# SatController_S1.net
KiCad netlist of a schematic drawn in Altium Designer
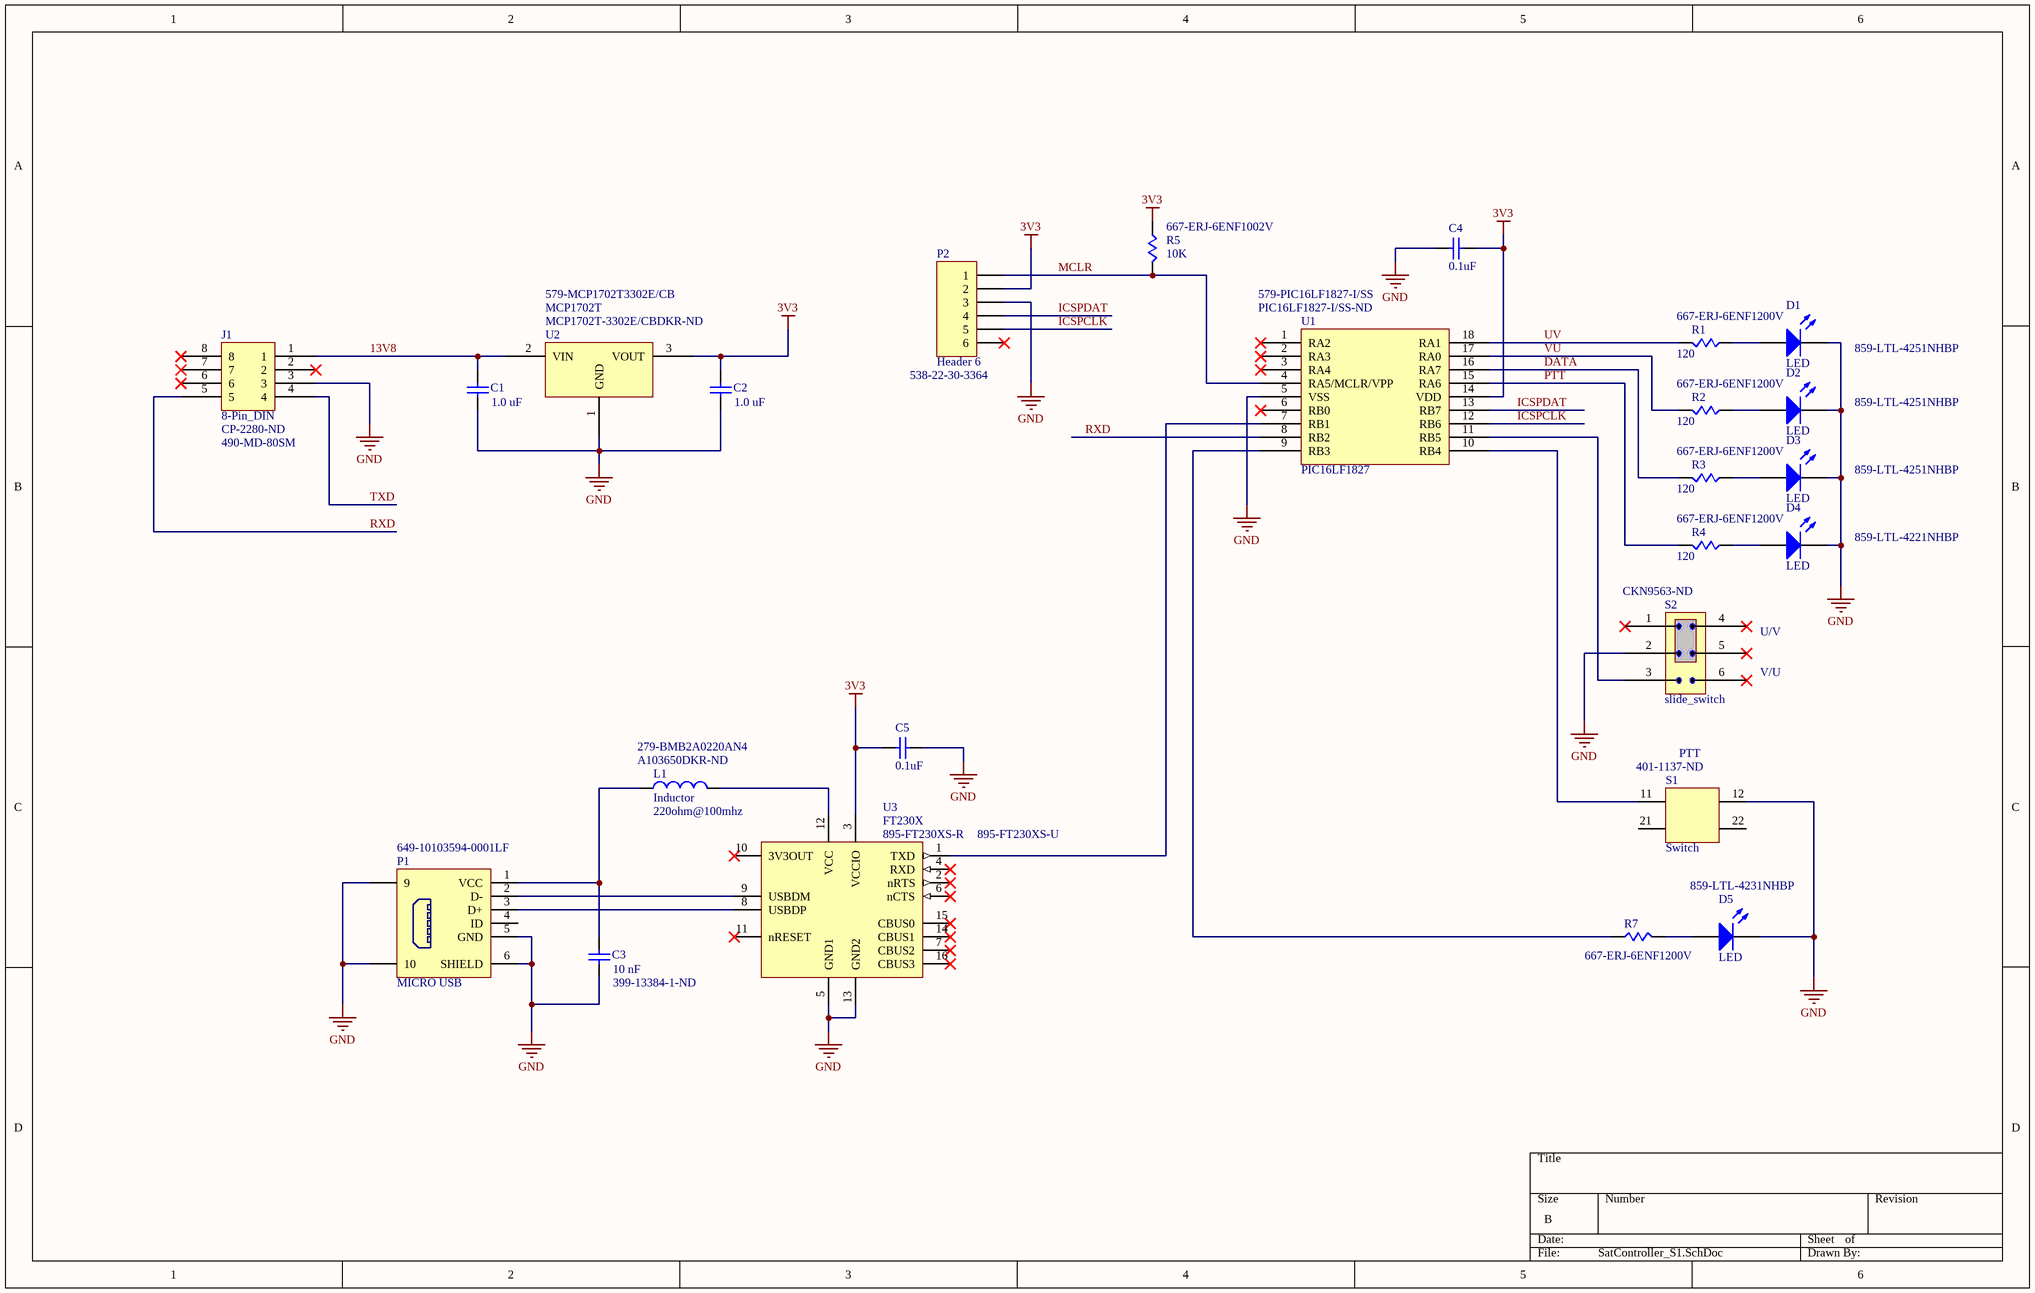
[diagram p0: SatController_S1.SchDoc]

(export (version "E")
  (design (tool "Eeschema 10.0.6"))
  (components
    (comp (ref "C1")
      (value "1.0 uF")
      (footprint "CAPC2012L")
      (libsource (lib "MAST_Library") (part "Cap Semi"))
    )
    (comp (ref "C2")
      (value "~")
      (footprint "CAPC2012L")
      (fields (field (name "VAULE") "1.0 uF"))
      (libsource (lib "MAST_Library") (part "Cap Semi"))
    )
    (comp (ref "C3")
      (value "10 nF")
      (footprint "CAPC1608L")
      (description "CAP CER 1UF 6.3V 10% X5R 0603")
      (fields
        (field (name "SUPPLIER PART NUMBER 1") "399-13384-1-ND")
        (field (name "MANUFACTURER") "Kemet")
        (field (name "MANUFACTURER PART NUMBER") "C0603C103J5JAC7867")
        (field (name "PUBLISHER") "Altium Limited")
      )
      (libsource (lib "MAST_Library") (part "Cap Semi"))
    )
    (comp (ref "C4")
      (value "0.1uF")
      (footprint "CAPC2012L")
      (libsource (lib "MAST_Library") (part "Cap Semi"))
    )
    (comp (ref "C5")
      (value "0.1uF")
      (footprint "CAPC2012L")
      (libsource (lib "MAST_Library") (part "Cap Semi"))
    )
    (comp (ref "D1")
      (value "LED")
      (footprint "LTL-4231HNBP")
      (description "SMD LED")
      (fields
        (field (name "SUPPLIER PART NUMBER 1") "859-LTL-4251NHBP")
        (field (name "MANUFACTURER") "Lite-On")
        (field (name "MANUFACTURER PART NUMBER") "LTL-4251NHBP")
      )
      (libsource (lib "Schlib_HCG") (part "LED3mm-ra"))
    )
    (comp (ref "D2")
      (value "LED")
      (footprint "LTL-4231HNBP")
      (description "SMD LED")
      (fields
        (field (name "SUPPLIER PART NUMBER 1") "859-LTL-4251NHBP")
        (field (name "MANUFACTURER") "Lite-On")
        (field (name "MANUFACTURER PART NUMBER") "LTL-4251NHBP")
      )
      (libsource (lib "Schlib_HCG") (part "LED3mm-ra"))
    )
    (comp (ref "D3")
      (value "LED")
      (footprint "LTL-4231HNBP")
      (description "SMD LED")
      (fields
        (field (name "SUPPLIER PART NUMBER 1") "859-LTL-4251NHBP")
        (field (name "MANUFACTURER") "Lite-On")
        (field (name "MANUFACTURER PART NUMBER") "LTL-4251NHBP")
      )
      (libsource (lib "Schlib_HCG") (part "LED3mm-ra"))
    )
    (comp (ref "D4")
      (value "LED")
      (footprint "LTL-4231HNBP")
      (description "SMD LED")
      (fields
        (field (name "SUPPLIER PART NUMBER 1") "859-LTL-4221NHBP")
        (field (name "MANUFACTURER") "Lite-On")
        (field (name "MANUFACTURER PART NUMBER") "LTL-4221NHBP")
      )
      (libsource (lib "Schlib_HCG") (part "LED3mm-ra"))
    )
    (comp (ref "D5")
      (value "LED")
      (footprint "LTL-4231HNBP")
      (description "SMD LED")
      (fields
        (field (name "SUPPLIER PART NUMBER 1") "859-LTL-4231NHBP")
        (field (name "MANUFACTURER") "Lite-On")
        (field (name "MANUFACTURER PART NUMBER") "LTL-4231NHBP")
      )
      (libsource (lib "Schlib_HCG") (part "LED3mm-ra"))
    )
    (comp (ref "J1")
      (value "8-Pin_DIN")
      (footprint "MD-80SM")
      (fields
        (field (name "SUPPLIER PART NUMBER 1") "CP-2280-ND")
        (field (name "SUPPLIER PART NUMBER 2") "490-MD-80SM")
        (field (name "MANUFACTURER") "CUI")
        (field (name "MANUFACTURER PART NUMBER") "MD-80SM")
      )
      (libsource (lib "Schlib_HCG") (part "8-Pin_DIN"))
    )
    (comp (ref "L1")
      (value "Inductor")
      (footprint "6-0805_N")
      (fields
        (field (name "ALTIUM_VALUE") "220ohm@100mhz")
        (field (name "SUPPLIER PART NUMBER 1") "A103650DKR-ND")
        (field (name "SUPPLIER PART NUMBER 2") "279-BMB2A0220AN4")
        (field (name "MANUFACTURER") "TE Connectivity / Sigma Inductors")
        (field (name "MANUFACTURER PART NUMBER") "BMB2A0220AN4")
        (field (name "TOLERANCE") "25 %")
        (field (name "PUBLISHER") "Altium Limited")
      )
      (libsource (lib "Miscellaneous Devices") (part "Inductor"))
    )
    (comp (ref "P1")
      (value "MICRO USB")
      (footprint "Connector, Micro-USB, 5-pin - prototype")
      (fields
        (field (name "SUPPLIER PART NUMBER 1") "649-10103594-0001LF")
        (field (name "MANUFACTURER") "Amphenol FCI")
        (field (name "MANUFACTURER PART NUMBER") "10103594-0001LF")
        (field (name "Comment") "Micro USB")
      )
      (libsource (lib "Schlib_HCG") (part "Micro USB"))
    )
    (comp (ref "P2")
      (value "Header 6")
      (footprint "HDR1X6")
      (description "Header, 6-Pin")
      (fields
        (field (name "SUPPLIER PART NUMBER 1") "538-22-30-3364")
        (field (name "MANUFACTURER") "Molex")
        (field (name "MANUFACTURER PART NUMBER") "22-30-3364")
        (field (name "PUBLISHER") "Altium Limited")
      )
      (libsource (lib "Schlib_HCG") (part "Header 6"))
    )
    (comp (ref "R1")
      (value "~")
      (footprint "RESC2012L")
      (description "RES 120 OHM 1/10W 1% 0402 SMD")
      (fields
        (field (name "SUPPLIER PART NUMBER 1") "667-ERJ-6ENF1200V")
        (field (name "MANUFACTURER") "Panasonic")
        (field (name "MANUFACTURER PART NUMBER") "ERJ-6ENF1200V")
        (field (name "VAULE") "120")
      )
      (libsource (lib "MAST_Library") (part "R"))
    )
    (comp (ref "R2")
      (value "~")
      (footprint "RESC2012L")
      (description "RES 120 OHM 1/10W 1% 0402 SMD")
      (fields
        (field (name "SUPPLIER PART NUMBER 1") "667-ERJ-6ENF1200V")
        (field (name "MANUFACTURER") "Panasonic")
        (field (name "MANUFACTURER PART NUMBER") "ERJ-6ENF1200V")
        (field (name "VAULE") "120")
      )
      (libsource (lib "MAST_Library") (part "R"))
    )
    (comp (ref "R3")
      (value "~")
      (footprint "RESC2012L")
      (description "RES 120 OHM 1/10W 1% 0402 SMD")
      (fields
        (field (name "SUPPLIER PART NUMBER 1") "667-ERJ-6ENF1200V")
        (field (name "MANUFACTURER") "Panasonic")
        (field (name "MANUFACTURER PART NUMBER") "ERJ-6ENF1200V")
        (field (name "VAULE") "120")
      )
      (libsource (lib "MAST_Library") (part "R"))
    )
    (comp (ref "R4")
      (value "~")
      (footprint "RESC2012L")
      (description "RES 120 OHM 1/10W 1% 0402 SMD")
      (fields
        (field (name "SUPPLIER PART NUMBER 1") "667-ERJ-6ENF1200V")
        (field (name "MANUFACTURER") "Panasonic")
        (field (name "MANUFACTURER PART NUMBER") "ERJ-6ENF1200V")
        (field (name "VAULE") "120")
      )
      (libsource (lib "MAST_Library") (part "R"))
    )
    (comp (ref "R5")
      (value "~")
      (footprint "RESC2012L")
      (description "RES 120 OHM 1/10W 1% 0402 SMD")
      (fields
        (field (name "VAULE") "10K")
        (field (name "SUPPLIER PART NUMBER 1") "667-ERJ-6ENF1002V")
        (field (name "MANUFACTURER") "Panasonic")
        (field (name "MANUFACTURER PART NUMBER") "ERJ-6ENF1002V")
      )
      (libsource (lib "MAST_Library") (part "R"))
    )
    (comp (ref "R7")
      (value "~")
      (footprint "RESC2012L")
      (description "RES 120 OHM 1/10W 1% 0402 SMD")
      (fields
        (field (name "SUPPLIER PART NUMBER 1") "667-ERJ-6ENF1200V")
        (field (name "MANUFACTURER") "Panasonic")
        (field (name "MANUFACTURER PART NUMBER") "ERJ-6ENF1200V")
      )
      (libsource (lib "MAST_Library") (part "R"))
    )
    (comp (ref "S1")
      (value "PVA-KeySwitch")
      (footprint "PVA1_Switch")
      (description "SWITCH PUSH DPST-NO 0.1A 32V")
      (fields
        (field (name "VAULE") "Switch")
        (field (name "SUPPLIER PART NUMBER 1") "401-1137-ND")
        (field (name "MANUFACTURER") "C&K Components")
        (field (name "MANUFACTURER PART NUMBER") "PVA1 OA H3 1.2N V2")
      )
      (libsource (lib "Schlib_HCG") (part "PVA-KeySwitch"))
    )
    (comp (ref "S2")
      (value "slide_switch")
      (footprint "OS202011MA0QN1")
      (description "SWITCH SLIDE DPDT 100MA 12V")
      (fields
        (field (name "SUPPLIER PART NUMBER 1") "CKN9563-ND")
        (field (name "MANUFACTURER") "C&K Components")
        (field (name "MANUFACTURER PART NUMBER") "OS202011MA0QN1")
      )
      (libsource (lib "Schlib_HCG") (part "slide_switch"))
    )
    (comp (ref "U1")
      (value "PIC16LF1827")
      (footprint "SOIC127P1030-18M")
      (fields
        (field (name "SUPPLIER PART NUMBER 2") "PIC16LF1827-I/SS-ND")
        (field (name "MANUFACTURER") "Microchip Technology")
        (field (name "MANUFACTURER PART NUMBER") "PIC16LF1827-I/SS")
        (field (name "SUPPLIER PART NUMBER 3") "579-PIC16LF1827-I/SS")
      )
      (libsource (lib "Schlib_HCG") (part "PIC16LF1827"))
    )
    (comp (ref "U2")
      (value "MCP1702T")
      (footprint "SOT23-3N")
      (fields
        (field (name "SUPPLIER PART NUMBER 1") "MCP1702T-3302E/CBDKR-ND")
        (field (name "SUPPLIER PART NUMBER 2") "579-MCP1702T3302E/CB")
        (field (name "MANUFACTURER") "Microchip Technology")
        (field (name "MANUFACTURER PART NUMBER") "MCP1702T-3302E/CB")
      )
      (libsource (lib "Schlib_HCG") (part "MCP1702T"))
    )
    (comp (ref "U3")
      (value "FT230X")
      (footprint "SOP64P600X175-16N")
      (fields
        (field (name "SUPPLIER PART NUMBER 1") "895-FT230XS-R")
        (field (name "SUPPLIER PART NUMBER 2") "895-FT230XS-U")
        (field (name "MANUFACTURER") "FTDI")
        (field (name "MANUFACTURER PART NUMBER") "FT230XS-U")
      )
      (libsource (lib "Schlib_HCG") (part "FT230X"))
    )
  )
  (nets
    (net (code "1") (name "/13V8") (class "Default")
      (node (ref "C1") (pin "2") (pinfunction "2_2") (pintype "passive"))
      (node (ref "J1") (pin "1") (pinfunction "1_1") (pintype "passive"))
      (node (ref "U2") (pin "2") (pinfunction "VIN_2") (pintype "passive"))
    )
    (net (code "2") (name "/DATA") (class "Default")
      (node (ref "R3") (pin "2") (pinfunction "2_2") (pintype "passive"))
      (node (ref "U1") (pin "16") (pinfunction "RA7_16") (pintype "passive"))
    )
    (net (code "3") (name "/ICSPCLK") (class "Default")
      (node (ref "P2") (pin "5") (pinfunction "5_5") (pintype "passive"))
      (node (ref "U1") (pin "12") (pinfunction "RB6_12") (pintype "passive"))
    )
    (net (code "4") (name "/ICSPDAT") (class "Default")
      (node (ref "P2") (pin "4") (pinfunction "4_4") (pintype "passive"))
      (node (ref "U1") (pin "13") (pinfunction "RB7_13") (pintype "passive"))
    )
    (net (code "5") (name "/MCLR") (class "Default")
      (node (ref "P2") (pin "1") (pinfunction "1_1") (pintype "passive"))
      (node (ref "R5") (pin "2") (pinfunction "2_2") (pintype "passive"))
      (node (ref "U1") (pin "4") (pinfunction "RA5/MCLR/VPP_4") (pintype "passive"))
    )
    (net (code "6") (name "/PTT") (class "Default")
      (node (ref "R4") (pin "2") (pinfunction "2_2") (pintype "passive"))
      (node (ref "U1") (pin "15") (pinfunction "RA6_15") (pintype "passive"))
    )
    (net (code "7") (name "/RXD") (class "Default")
      (node (ref "J1") (pin "5") (pinfunction "5_5") (pintype "passive"))
      (node (ref "U1") (pin "8") (pinfunction "RB2_8") (pintype "passive"))
    )
    (net (code "8") (name "/TXD") (class "Default")
      (node (ref "J1") (pin "4") (pinfunction "4_4") (pintype "passive"))
    )
    (net (code "9") (name "/UV") (class "Default")
      (node (ref "R1") (pin "2") (pinfunction "2_2") (pintype "passive"))
      (node (ref "U1") (pin "18") (pinfunction "RA1_18") (pintype "passive"))
    )
    (net (code "10") (name "/VU") (class "Default")
      (node (ref "R2") (pin "2") (pinfunction "2_2") (pintype "passive"))
      (node (ref "U1") (pin "17") (pinfunction "RA0_17") (pintype "passive"))
    )
    (net (code "11") (name "3V3") (class "Default")
      (node (ref "C2") (pin "2") (pinfunction "2_2") (pintype "passive"))
      (node (ref "C4") (pin "1") (pinfunction "1_1") (pintype "passive"))
      (node (ref "C5") (pin "2") (pinfunction "2_2") (pintype "passive"))
      (node (ref "P2") (pin "2") (pinfunction "2_2") (pintype "passive"))
      (node (ref "R5") (pin "1") (pinfunction "1_1") (pintype "passive"))
      (node (ref "U1") (pin "14") (pinfunction "VDD_14") (pintype "passive"))
      (node (ref "U2") (pin "3") (pinfunction "VOUT_3") (pintype "passive"))
      (node (ref "U3") (pin "3") (pinfunction "VCCIO_3") (pintype "passive"))
    )
    (net (code "12") (name "GND") (class "Default")
      (node (ref "C1") (pin "1") (pinfunction "1_1") (pintype "passive"))
      (node (ref "C2") (pin "1") (pinfunction "1_1") (pintype "passive"))
      (node (ref "C3") (pin "1") (pinfunction "1_1") (pintype "passive"))
      (node (ref "C4") (pin "2") (pinfunction "2_2") (pintype "passive"))
      (node (ref "C5") (pin "1") (pinfunction "1_1") (pintype "passive"))
      (node (ref "D1") (pin "2") (pinfunction "K_2") (pintype "passive"))
      (node (ref "D2") (pin "2") (pinfunction "K_2") (pintype "passive"))
      (node (ref "D3") (pin "2") (pinfunction "K_2") (pintype "passive"))
      (node (ref "D4") (pin "2") (pinfunction "K_2") (pintype "passive"))
      (node (ref "D5") (pin "2") (pinfunction "K_2") (pintype "passive"))
      (node (ref "J1") (pin "3") (pinfunction "3_3") (pintype "passive"))
      (node (ref "P1") (pin "10") (pinfunction "10_10") (pintype "passive"))
      (node (ref "P1") (pin "5") (pinfunction "GND_5") (pintype "passive"))
      (node (ref "P1") (pin "6") (pinfunction "SHIELD_6") (pintype "passive"))
      (node (ref "P1") (pin "9") (pinfunction "9_9") (pintype "passive"))
      (node (ref "P2") (pin "3") (pinfunction "3_3") (pintype "passive"))
      (node (ref "S1") (pin "12") (pinfunction "12_12") (pintype "passive"))
      (node (ref "S2") (pin "2") (pinfunction "2_2") (pintype "passive"))
      (node (ref "U1") (pin "5") (pinfunction "VSS_5") (pintype "passive"))
      (node (ref "U2") (pin "1") (pinfunction "GND_1") (pintype "passive"))
      (node (ref "U3") (pin "13") (pinfunction "GND2_13") (pintype "passive"))
      (node (ref "U3") (pin "5") (pinfunction "GND1_5") (pintype "passive"))
    )
    (net (code "13") (name "Net-(D1-A)") (class "Default")
      (node (ref "D1") (pin "1") (pinfunction "A_1") (pintype "passive"))
      (node (ref "R1") (pin "1") (pinfunction "1_1") (pintype "passive"))
    )
    (net (code "14") (name "Net-(D2-A)") (class "Default")
      (node (ref "D2") (pin "1") (pinfunction "A_1") (pintype "passive"))
      (node (ref "R2") (pin "1") (pinfunction "1_1") (pintype "passive"))
    )
    (net (code "15") (name "Net-(D3-A)") (class "Default")
      (node (ref "D3") (pin "1") (pinfunction "A_1") (pintype "passive"))
      (node (ref "R3") (pin "1") (pinfunction "1_1") (pintype "passive"))
    )
    (net (code "16") (name "Net-(D4-A)") (class "Default")
      (node (ref "D4") (pin "1") (pinfunction "A_1") (pintype "passive"))
      (node (ref "R4") (pin "1") (pinfunction "1_1") (pintype "passive"))
    )
    (net (code "17") (name "Net-(D5-A)") (class "Default")
      (node (ref "D5") (pin "1") (pinfunction "A_1") (pintype "passive"))
      (node (ref "R7") (pin "2") (pinfunction "2_2") (pintype "passive"))
    )
    (net (code "18") (name "Net-(P1-D+)") (class "Default")
      (node (ref "P1") (pin "3") (pinfunction "D+_3") (pintype "passive"))
      (node (ref "U3") (pin "8") (pinfunction "USBDP_8") (pintype "passive"))
    )
    (net (code "19") (name "Net-(P1-D-)") (class "Default")
      (node (ref "P1") (pin "2") (pinfunction "D-_2") (pintype "passive"))
      (node (ref "U3") (pin "9") (pinfunction "USBDM_9") (pintype "passive"))
    )
    (net (code "20") (name "Net-(P1-VCC)") (class "Default")
      (node (ref "C3") (pin "2") (pinfunction "2_2") (pintype "passive"))
      (node (ref "L1") (pin "1") (pinfunction "1_1") (pintype "passive"))
      (node (ref "P1") (pin "1") (pinfunction "VCC_1") (pintype "passive"))
    )
    (net (code "21") (name "Net-(U1-RB1)") (class "Default")
      (node (ref "U1") (pin "7") (pinfunction "RB1_7") (pintype "passive"))
      (node (ref "U3") (pin "1") (pinfunction "TXD_1") (pintype "output"))
    )
    (net (code "22") (name "Net-(U1-RB3)") (class "Default")
      (node (ref "R7") (pin "1") (pinfunction "1_1") (pintype "passive"))
      (node (ref "U1") (pin "9") (pinfunction "RB3_9") (pintype "passive"))
    )
    (net (code "23") (name "Net-(U1-RB4)") (class "Default")
      (node (ref "S1") (pin "11") (pinfunction "11_11") (pintype "passive"))
      (node (ref "U1") (pin "10") (pinfunction "RB4_10") (pintype "passive"))
    )
    (net (code "24") (name "Net-(U1-RB5)") (class "Default")
      (node (ref "S2") (pin "3") (pinfunction "3_3") (pintype "passive"))
      (node (ref "U1") (pin "11") (pinfunction "RB5_11") (pintype "passive"))
    )
    (net (code "25") (name "Net-(U3-VCC)") (class "Default")
      (node (ref "L1") (pin "2") (pinfunction "2_2") (pintype "passive"))
      (node (ref "U3") (pin "12") (pinfunction "VCC_12") (pintype "passive"))
    )
    (net (code "26") (name "unconnected-(J1-Pad2)") (class "Default")
      (node (ref "J1") (pin "2") (pinfunction "2_2") (pintype "passive+no_connect"))
    )
    (net (code "27") (name "unconnected-(J1-Pad6)") (class "Default")
      (node (ref "J1") (pin "6") (pinfunction "6_6") (pintype "passive+no_connect"))
    )
    (net (code "28") (name "unconnected-(J1-Pad7)") (class "Default")
      (node (ref "J1") (pin "7") (pinfunction "7_7") (pintype "passive+no_connect"))
    )
    (net (code "29") (name "unconnected-(J1-Pad8)") (class "Default")
      (node (ref "J1") (pin "8") (pinfunction "8_8") (pintype "passive+no_connect"))
    )
    (net (code "30") (name "unconnected-(P1-ID-Pad4)") (class "Default")
      (node (ref "P1") (pin "4") (pinfunction "ID_4") (pintype "passive"))
    )
    (net (code "31") (name "unconnected-(P2-Pad6)") (class "Default")
      (node (ref "P2") (pin "6") (pinfunction "6_6") (pintype "passive+no_connect"))
    )
    (net (code "32") (name "unconnected-(S1-Pad21)") (class "Default")
      (node (ref "S1") (pin "21") (pinfunction "21_21") (pintype "passive"))
    )
    (net (code "33") (name "unconnected-(S1-Pad22)") (class "Default")
      (node (ref "S1") (pin "22") (pinfunction "22_22") (pintype "passive"))
    )
    (net (code "34") (name "unconnected-(S2-Pad1)") (class "Default")
      (node (ref "S2") (pin "1") (pinfunction "1_1") (pintype "passive+no_connect"))
    )
    (net (code "35") (name "unconnected-(S2-Pad4)") (class "Default")
      (node (ref "S2") (pin "4") (pinfunction "4_4") (pintype "passive+no_connect"))
    )
    (net (code "36") (name "unconnected-(S2-Pad5)") (class "Default")
      (node (ref "S2") (pin "5") (pinfunction "5_5") (pintype "passive+no_connect"))
    )
    (net (code "37") (name "unconnected-(S2-Pad6)") (class "Default")
      (node (ref "S2") (pin "6") (pinfunction "6_6") (pintype "passive+no_connect"))
    )
    (net (code "38") (name "unconnected-(U1-RA2-Pad1)") (class "Default")
      (node (ref "U1") (pin "1") (pinfunction "RA2_1") (pintype "passive+no_connect"))
    )
    (net (code "39") (name "unconnected-(U1-RA3-Pad2)") (class "Default")
      (node (ref "U1") (pin "2") (pinfunction "RA3_2") (pintype "passive+no_connect"))
    )
    (net (code "40") (name "unconnected-(U1-RA4-Pad3)") (class "Default")
      (node (ref "U1") (pin "3") (pinfunction "RA4_3") (pintype "passive+no_connect"))
    )
    (net (code "41") (name "unconnected-(U1-RB0-Pad6)") (class "Default")
      (node (ref "U1") (pin "6") (pinfunction "RB0_6") (pintype "passive+no_connect"))
    )
    (net (code "42") (name "unconnected-(U3-3V3OUT-Pad10)") (class "Default")
      (node (ref "U3") (pin "10") (pinfunction "3V3OUT_10") (pintype "passive+no_connect"))
    )
    (net (code "43") (name "unconnected-(U3-CBUS0-Pad15)") (class "Default")
      (node (ref "U3") (pin "15") (pinfunction "CBUS0_15") (pintype "passive+no_connect"))
    )
    (net (code "44") (name "unconnected-(U3-CBUS1-Pad14)") (class "Default")
      (node (ref "U3") (pin "14") (pinfunction "CBUS1_14") (pintype "passive+no_connect"))
    )
    (net (code "45") (name "unconnected-(U3-CBUS2-Pad7)") (class "Default")
      (node (ref "U3") (pin "7") (pinfunction "CBUS2_7") (pintype "passive+no_connect"))
    )
    (net (code "46") (name "unconnected-(U3-CBUS3-Pad16)") (class "Default")
      (node (ref "U3") (pin "16") (pinfunction "CBUS3_16") (pintype "passive+no_connect"))
    )
    (net (code "47") (name "unconnected-(U3-RXD-Pad4)") (class "Default")
      (node (ref "U3") (pin "4") (pinfunction "RXD_4") (pintype "input+no_connect"))
    )
    (net (code "48") (name "unconnected-(U3-nCTS-Pad6)") (class "Default")
      (node (ref "U3") (pin "6") (pinfunction "nCTS_6") (pintype "input+no_connect"))
    )
    (net (code "49") (name "unconnected-(U3-nRESET-Pad11)") (class "Default")
      (node (ref "U3") (pin "11") (pinfunction "nRESET_11") (pintype "passive+no_connect"))
    )
    (net (code "50") (name "unconnected-(U3-nRTS-Pad2)") (class "Default")
      (node (ref "U3") (pin "2") (pinfunction "nRTS_2") (pintype "output+no_connect"))
    )
  )
)
